# Wash_Hand_v1.net
KiCad netlist of a schematic drawn in EAGLE
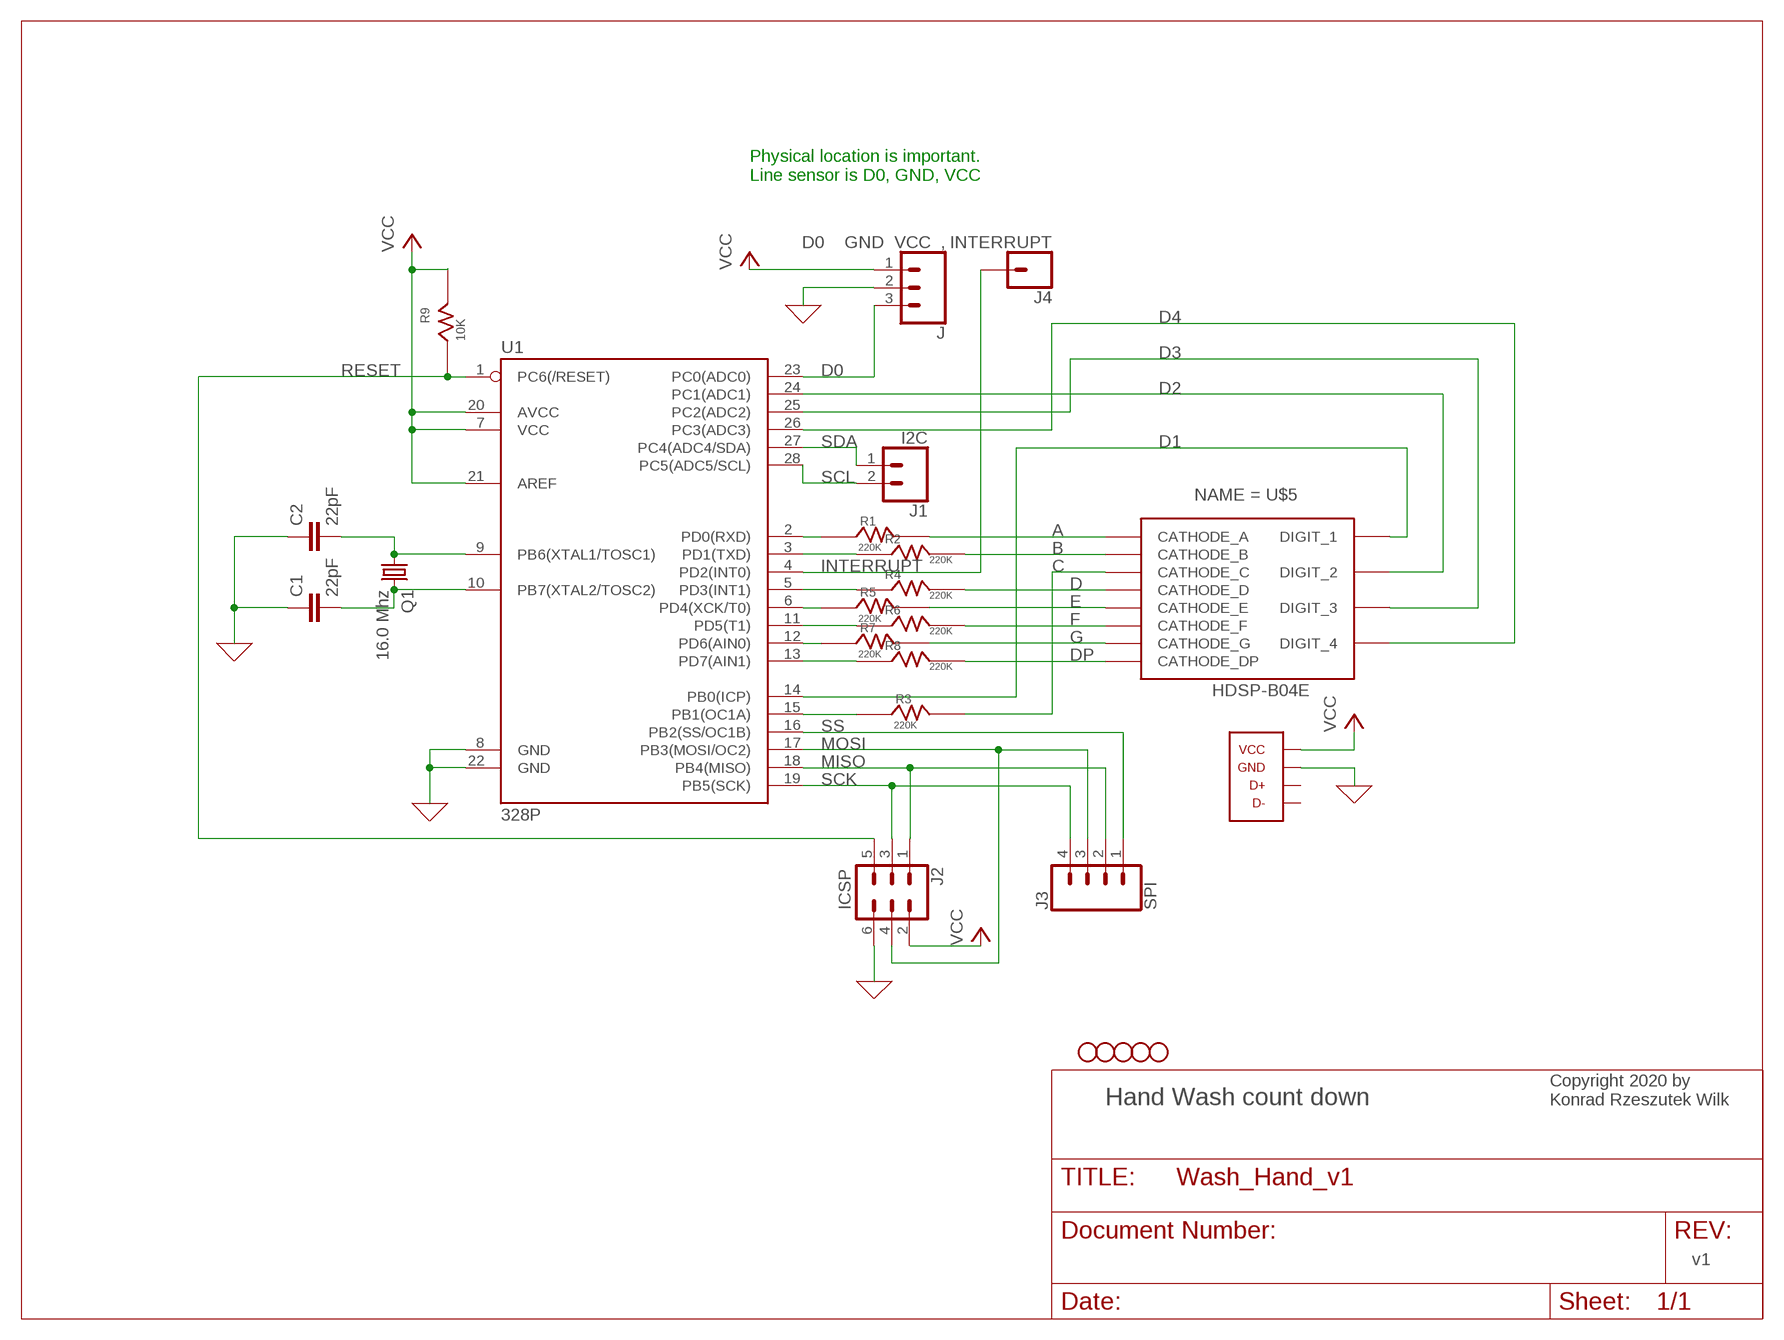
[diagram p0: schematic, sheet 1]

(export (version "E")
  (design (tool "Eeschema 10.0.6"))
  (components
    (comp (ref "C1")
      (value "22pF")
      (footprint "eagle-import:CAP-PTH-2.54")
      (libsource (lib "eagle-import") (part "22PF-PTH-2.54MM-200V-5%"))
    )
    (comp (ref "C2")
      (value "22pF")
      (footprint "eagle-import:CAP-PTH-2.54")
      (libsource (lib "eagle-import") (part "22PF-PTH-2.54MM-200V-5%"))
    )
    (comp (ref "H1")
      (value "STAND-OFF")
      (footprint "eagle-import:STAND-OFF")
      (libsource (lib "eagle-import") (part "STAND-OFF"))
    )
    (comp (ref "H2")
      (value "STAND-OFF")
      (footprint "eagle-import:STAND-OFF")
      (libsource (lib "eagle-import") (part "STAND-OFF"))
    )
    (comp (ref "H3")
      (value "STAND-OFF")
      (footprint "eagle-import:STAND-OFF")
      (libsource (lib "eagle-import") (part "STAND-OFF"))
    )
    (comp (ref "H4")
      (value "STAND-OFF")
      (footprint "eagle-import:STAND-OFF")
      (libsource (lib "eagle-import") (part "STAND-OFF"))
    )
    (comp (ref "H5")
      (value "STAND-OFF")
      (footprint "eagle-import:STAND-OFF")
      (libsource (lib "eagle-import") (part "STAND-OFF"))
    )
    (comp (ref "J")
      (value "D0 GND VCC ,")
      (footprint "eagle-import:1X03")
      (libsource (lib "eagle-import") (part "CONN_03"))
    )
    (comp (ref "J1")
      (value "I2C")
      (footprint "eagle-import:1X02")
      (libsource (lib "eagle-import") (part "CONN_02"))
    )
    (comp (ref "J2")
      (value "ICSP")
      (footprint "eagle-import:2X3")
      (libsource (lib "eagle-import") (part "CONN_03X2FEMALE"))
    )
    (comp (ref "J3")
      (value "SPI")
      (footprint "eagle-import:1X04")
      (libsource (lib "eagle-import") (part "CONN_04"))
    )
    (comp (ref "J4")
      (value "INTERRUPT")
      (footprint "eagle-import:1X01")
      (libsource (lib "eagle-import") (part "CONN_01"))
    )
    (comp (ref "Q1")
      (value "16.0 Mhz")
      (footprint "eagle-import:HC49_S")
      (libsource (lib "eagle-import") (part "CRYSTALHC49S"))
    )
    (comp (ref "R1")
      (value "220K")
      (footprint "eagle-import:RESISTOR")
      (libsource (lib "eagle-import") (part "RESISTOR"))
    )
    (comp (ref "R2")
      (value "220K")
      (footprint "eagle-import:RESISTOR")
      (libsource (lib "eagle-import") (part "RESISTOR"))
    )
    (comp (ref "R3")
      (value "220K")
      (footprint "eagle-import:RESISTOR")
      (libsource (lib "eagle-import") (part "RESISTOR"))
    )
    (comp (ref "R4")
      (value "220K")
      (footprint "eagle-import:RESISTOR")
      (libsource (lib "eagle-import") (part "RESISTOR"))
    )
    (comp (ref "R5")
      (value "220K")
      (footprint "eagle-import:RESISTOR")
      (libsource (lib "eagle-import") (part "RESISTOR"))
    )
    (comp (ref "R6")
      (value "220K")
      (footprint "eagle-import:RESISTOR")
      (libsource (lib "eagle-import") (part "RESISTOR"))
    )
    (comp (ref "R7")
      (value "220K")
      (footprint "eagle-import:RESISTOR")
      (libsource (lib "eagle-import") (part "RESISTOR"))
    )
    (comp (ref "R8")
      (value "220K")
      (footprint "eagle-import:RESISTOR")
      (libsource (lib "eagle-import") (part "RESISTOR"))
    )
    (comp (ref "R9")
      (value "10K")
      (footprint "eagle-import:RESISTOR")
      (libsource (lib "eagle-import") (part "RESISTOR"))
    )
    (comp (ref "U$4")
      (value "USB_MICROB_10118194_AMPHENOL")
      (footprint "eagle-import:USB_MICROB_10118194_AMPHENOL")
      (libsource (lib "eagle-import") (part "USB_MICROB_10118194_AMPHENOL"))
    )
    (comp (ref "U$5")
      (value "HDSP-B04E")
      (footprint "eagle-import:HDSP-B0XE")
      (libsource (lib "eagle-import") (part "HDSP-B04E"))
    )
    (comp (ref "U1")
      (value "328P")
      (footprint "eagle-import:DIP28")
      (libsource (lib "eagle-import") (part "ATMEGA328P_PDIP"))
    )
  )
  (nets
    (net (code "1") (name "/A") (class "Default")
      (node (ref "R1") (pin "R_2") (pinfunction "R_2_R_2") (pintype "bidirectional"))
      (node (ref "U$5") (pin "PIN$11") (pinfunction "CATHODE_A_PIN$11") (pintype "input"))
    )
    (net (code "2") (name "/B") (class "Default")
      (node (ref "R2") (pin "R_2") (pinfunction "R_2_R_2") (pintype "bidirectional"))
      (node (ref "U$5") (pin "PIN$7") (pinfunction "CATHODE_B_PIN$7") (pintype "input"))
    )
    (net (code "3") (name "/C") (class "Default")
      (node (ref "R3") (pin "R_2") (pinfunction "R_2_R_2") (pintype "bidirectional"))
      (node (ref "U$5") (pin "PIN$4") (pinfunction "CATHODE_C_PIN$4") (pintype "input"))
    )
    (net (code "4") (name "/D") (class "Default")
      (node (ref "R4") (pin "R_2") (pinfunction "R_2_R_2") (pintype "bidirectional"))
      (node (ref "U$5") (pin "PIN$2") (pinfunction "CATHODE_D_PIN$2") (pintype "input"))
    )
    (net (code "5") (name "/D0") (class "Default")
      (node (ref "J") (pin "3") (pinfunction "3_3") (pintype "passive"))
      (node (ref "U1") (pin "23") (pinfunction "PC0(ADC0)_23") (pintype "bidirectional"))
    )
    (net (code "6") (name "/D1") (class "Default")
      (node (ref "U$5") (pin "PIN12") (pinfunction "DIGIT_1_PIN12") (pintype "input"))
      (node (ref "U1") (pin "14") (pinfunction "PB0(ICP)_14") (pintype "bidirectional"))
    )
    (net (code "7") (name "/D2") (class "Default")
      (node (ref "U$5") (pin "PIN$9") (pinfunction "DIGIT_2_PIN$9") (pintype "input"))
      (node (ref "U1") (pin "24") (pinfunction "PC1(ADC1)_24") (pintype "bidirectional"))
    )
    (net (code "8") (name "/D3") (class "Default")
      (node (ref "U$5") (pin "PIN$8") (pinfunction "DIGIT_3_PIN$8") (pintype "input"))
      (node (ref "U1") (pin "25") (pinfunction "PC2(ADC2)_25") (pintype "bidirectional"))
    )
    (net (code "9") (name "/D4") (class "Default")
      (node (ref "U$5") (pin "PIN$6") (pinfunction "DIGIT_4_PIN$6") (pintype "input"))
      (node (ref "U1") (pin "26") (pinfunction "PC3(ADC3)_26") (pintype "bidirectional"))
    )
    (net (code "10") (name "/DP") (class "Default")
      (node (ref "R8") (pin "R_2") (pinfunction "R_2_R_2") (pintype "bidirectional"))
      (node (ref "U$5") (pin "PIN$3") (pinfunction "CATHODE_DP_PIN$3") (pintype "input"))
    )
    (net (code "11") (name "/E") (class "Default")
      (node (ref "R5") (pin "R_2") (pinfunction "R_2_R_2") (pintype "bidirectional"))
      (node (ref "U$5") (pin "PIN$1") (pinfunction "CATHODE_E_PIN$1") (pintype "input"))
    )
    (net (code "12") (name "/F") (class "Default")
      (node (ref "R6") (pin "R_2") (pinfunction "R_2_R_2") (pintype "bidirectional"))
      (node (ref "U$5") (pin "PIN$10") (pinfunction "CATHODE_F_PIN$10") (pintype "input"))
    )
    (net (code "13") (name "/G") (class "Default")
      (node (ref "R7") (pin "R_2") (pinfunction "R_2_R_2") (pintype "bidirectional"))
      (node (ref "U$5") (pin "PIN$5") (pinfunction "CATHODE_G_PIN$5") (pintype "input"))
    )
    (net (code "14") (name "/INTERRUPT") (class "Default")
      (node (ref "J4") (pin "1") (pinfunction "1_1") (pintype "passive"))
      (node (ref "U1") (pin "4") (pinfunction "PD2(INT0)_4") (pintype "bidirectional"))
    )
    (net (code "15") (name "/MISO") (class "Default")
      (node (ref "J2") (pin "1") (pinfunction "1_1") (pintype "bidirectional"))
      (node (ref "J3") (pin "2") (pinfunction "2_2") (pintype "passive"))
      (node (ref "U1") (pin "18") (pinfunction "PB4(MISO)_18") (pintype "bidirectional"))
    )
    (net (code "16") (name "/MOSI") (class "Default")
      (node (ref "J2") (pin "4") (pinfunction "4_4") (pintype "bidirectional"))
      (node (ref "J3") (pin "3") (pinfunction "3_3") (pintype "passive"))
      (node (ref "U1") (pin "17") (pinfunction "PB3(MOSI/OC2)_17") (pintype "bidirectional"))
    )
    (net (code "17") (name "/RESET") (class "Default")
      (node (ref "J2") (pin "5") (pinfunction "5_5") (pintype "bidirectional"))
      (node (ref "R9") (pin "R_1") (pinfunction "R_1_R_1") (pintype "bidirectional"))
      (node (ref "U1") (pin "1") (pinfunction "PC6(/RESET)_1") (pintype "bidirectional"))
    )
    (net (code "18") (name "/SCK") (class "Default")
      (node (ref "J2") (pin "3") (pinfunction "3_3") (pintype "bidirectional"))
      (node (ref "J3") (pin "4") (pinfunction "4_4") (pintype "passive"))
      (node (ref "U1") (pin "19") (pinfunction "PB5(SCK)_19") (pintype "bidirectional"))
    )
    (net (code "19") (name "/SCL") (class "Default")
      (node (ref "J1") (pin "2") (pinfunction "2_2") (pintype "passive"))
      (node (ref "U1") (pin "28") (pinfunction "PC5(ADC5/SCL)_28") (pintype "bidirectional"))
    )
    (net (code "20") (name "/SDA") (class "Default")
      (node (ref "J1") (pin "1") (pinfunction "1_1") (pintype "passive"))
      (node (ref "U1") (pin "27") (pinfunction "PC4(ADC4/SDA)_27") (pintype "bidirectional"))
    )
    (net (code "21") (name "/SS") (class "Default")
      (node (ref "J3") (pin "1") (pinfunction "1_1") (pintype "passive"))
      (node (ref "U1") (pin "16") (pinfunction "PB2(SS/OC1B)_16") (pintype "bidirectional"))
    )
    (net (code "22") (name "GND") (class "Default")
      (node (ref "C1") (pin "1") (pinfunction "1_1") (pintype "passive"))
      (node (ref "C2") (pin "1") (pinfunction "1_1") (pintype "passive"))
      (node (ref "J") (pin "2") (pinfunction "2_2") (pintype "passive"))
      (node (ref "J2") (pin "6") (pinfunction "6_6") (pintype "bidirectional"))
      (node (ref "U$4") (pin "5") (pinfunction "GND_5") (pintype "bidirectional"))
      (node (ref "U1") (pin "22") (pinfunction "GND_22") (pintype "bidirectional"))
      (node (ref "U1") (pin "8") (pinfunction "GND_8") (pintype "bidirectional"))
    )
    (net (code "23") (name "Net-(U1-PB1(OC1A))") (class "Default")
      (node (ref "R3") (pin "R_1") (pinfunction "R_1_R_1") (pintype "bidirectional"))
      (node (ref "U1") (pin "15") (pinfunction "PB1(OC1A)_15") (pintype "bidirectional"))
    )
    (net (code "24") (name "Net-(U1-PB6(XTAL1{slash}TOSC1))") (class "Default")
      (node (ref "C2") (pin "2") (pinfunction "2_2") (pintype "passive"))
      (node (ref "Q1") (pin "1") (pinfunction "1_1") (pintype "passive"))
      (node (ref "U1") (pin "9") (pinfunction "PB6(XTAL1/TOSC1)_9") (pintype "bidirectional"))
    )
    (net (code "25") (name "Net-(U1-PB7(XTAL2{slash}TOSC2))") (class "Default")
      (node (ref "C1") (pin "2") (pinfunction "2_2") (pintype "passive"))
      (node (ref "Q1") (pin "2") (pinfunction "2_2") (pintype "passive"))
      (node (ref "U1") (pin "10") (pinfunction "PB7(XTAL2/TOSC2)_10") (pintype "bidirectional"))
    )
    (net (code "26") (name "Net-(U1-PD0(RXD))") (class "Default")
      (node (ref "R1") (pin "R_1") (pinfunction "R_1_R_1") (pintype "bidirectional"))
      (node (ref "U1") (pin "2") (pinfunction "PD0(RXD)_2") (pintype "bidirectional"))
    )
    (net (code "27") (name "Net-(U1-PD1(TXD))") (class "Default")
      (node (ref "R2") (pin "R_1") (pinfunction "R_1_R_1") (pintype "bidirectional"))
      (node (ref "U1") (pin "3") (pinfunction "PD1(TXD)_3") (pintype "bidirectional"))
    )
    (net (code "28") (name "Net-(U1-PD3(INT1))") (class "Default")
      (node (ref "R4") (pin "R_1") (pinfunction "R_1_R_1") (pintype "bidirectional"))
      (node (ref "U1") (pin "5") (pinfunction "PD3(INT1)_5") (pintype "bidirectional"))
    )
    (net (code "29") (name "Net-(U1-PD4(XCK{slash}T0))") (class "Default")
      (node (ref "R5") (pin "R_1") (pinfunction "R_1_R_1") (pintype "bidirectional"))
      (node (ref "U1") (pin "6") (pinfunction "PD4(XCK/T0)_6") (pintype "bidirectional"))
    )
    (net (code "30") (name "Net-(U1-PD5(T1))") (class "Default")
      (node (ref "R6") (pin "R_1") (pinfunction "R_1_R_1") (pintype "bidirectional"))
      (node (ref "U1") (pin "11") (pinfunction "PD5(T1)_11") (pintype "bidirectional"))
    )
    (net (code "31") (name "Net-(U1-PD6(AIN0))") (class "Default")
      (node (ref "R7") (pin "R_1") (pinfunction "R_1_R_1") (pintype "bidirectional"))
      (node (ref "U1") (pin "12") (pinfunction "PD6(AIN0)_12") (pintype "bidirectional"))
    )
    (net (code "32") (name "Net-(U1-PD7(AIN1))") (class "Default")
      (node (ref "R8") (pin "R_1") (pinfunction "R_1_R_1") (pintype "bidirectional"))
      (node (ref "U1") (pin "13") (pinfunction "PD7(AIN1)_13") (pintype "bidirectional"))
    )
    (net (code "33") (name "VCC") (class "Default")
      (node (ref "J") (pin "1") (pinfunction "1_1") (pintype "passive"))
      (node (ref "J2") (pin "2") (pinfunction "2_2") (pintype "bidirectional"))
      (node (ref "R9") (pin "R_2") (pinfunction "R_2_R_2") (pintype "bidirectional"))
      (node (ref "U$4") (pin "1") (pinfunction "VCC_1") (pintype "bidirectional"))
      (node (ref "U1") (pin "20") (pinfunction "AVCC_20") (pintype "bidirectional"))
      (node (ref "U1") (pin "21") (pinfunction "AREF_21") (pintype "bidirectional"))
      (node (ref "U1") (pin "7") (pinfunction "VCC_7") (pintype "bidirectional"))
    )
    (net (code "34") (name "unconnected-(U$4-D+-Pad3)") (class "Default")
      (node (ref "U$4") (pin "3") (pinfunction "D+_3") (pintype "bidirectional"))
    )
    (net (code "35") (name "unconnected-(U$4-D--Pad2)") (class "Default")
      (node (ref "U$4") (pin "2") (pinfunction "D-_2") (pintype "bidirectional"))
    )
  )
)
